# rw-directish-mk-1_0.net
KiCad netlist of a schematic drawn in EAGLE
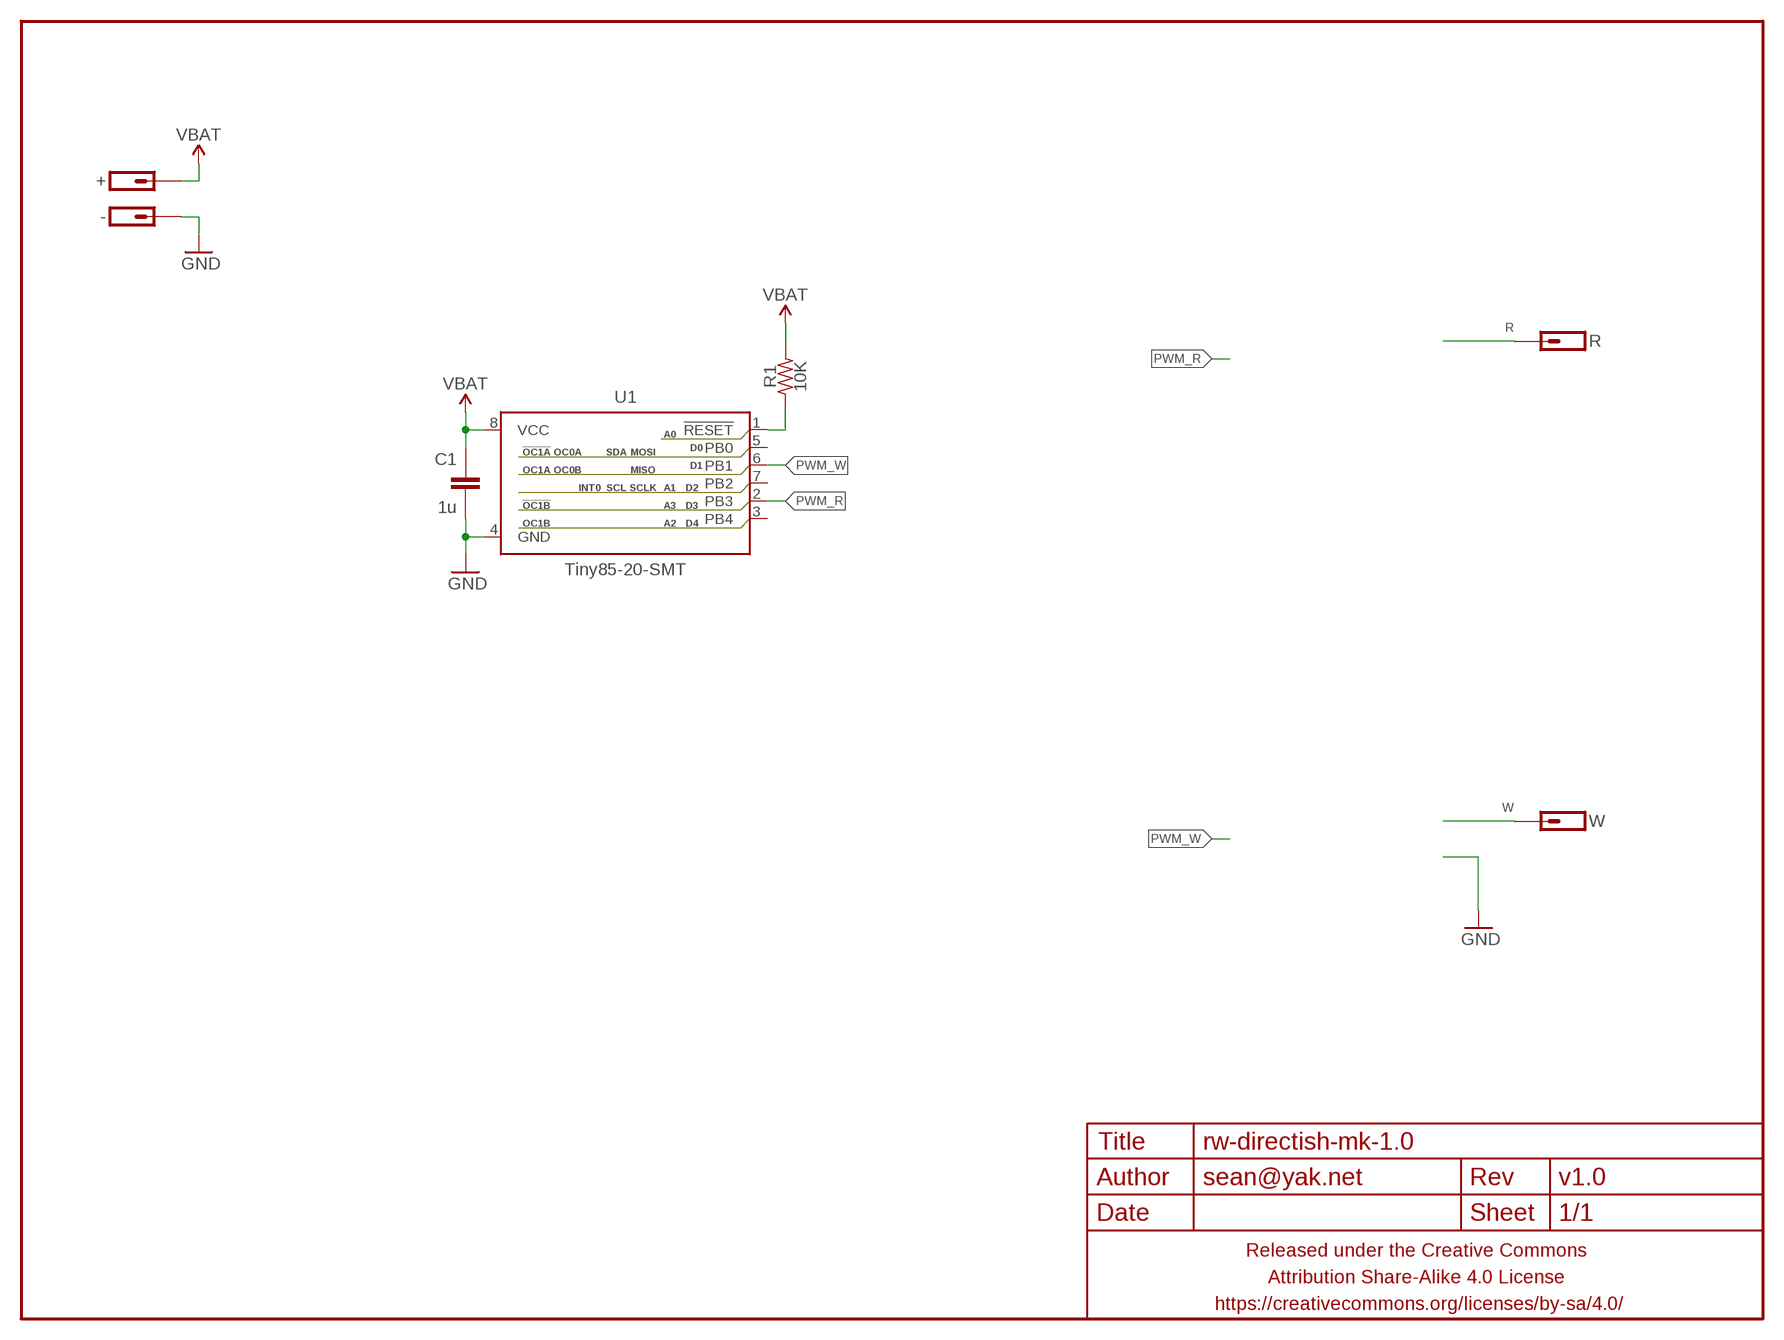
[diagram p0: schematic, sheet 1]

(export (version "E")
  (design (tool "Eeschema 10.0.6"))
  (components
    (comp (ref "+")
      (value "M01PTH-1.2MM-NS")
      (footprint "eagle-import:1X01-1.2MM-NS")
      (libsource (lib "eagle-import") (part "M01PTH-1.2MM-NS"))
    )
    (comp (ref "-")
      (value "M01NOT-A-VIA-NOPE")
      (footprint "eagle-import:1X01_NOSILK_NOSTOP")
      (libsource (lib "eagle-import") (part "M01NOT-A-VIA-NOPE"))
    )
    (comp (ref "C1")
      (value "1u")
      (footprint "eagle-import:C0402")
      (libsource (lib "eagle-import") (part "CAPACITOR-CERAMICC0402"))
    )
    (comp (ref "FRAME1")
      (value "FRAME-LETTERNO_PACKAGE")
      (footprint "eagle-import:DUMMY")
      (fields (field (name "DESIGNER") "sean@yak.net") (field (name "VERSION") "v1.0"))
      (libsource (lib "eagle-import") (part "FRAME-LETTERNO_PACKAGE"))
    )
    (comp (ref "R")
      (value "M01SMD-1.25MM-DIA")
      (footprint "eagle-import:1X01-SMD-1.25MM-DIA-NS")
      (libsource (lib "eagle-import") (part "M01SMD-1.25MM-DIA"))
    )
    (comp (ref "R1")
      (value "10K")
      (footprint "eagle-import:R0402")
      (libsource (lib "eagle-import") (part "RESISTORR0402"))
    )
    (comp (ref "U1")
      (value "Tiny85-20-SMT")
      (footprint "eagle-import:SO08-EIAJ")
      (libsource (lib "eagle-import") (part "ATTINY45TINY85-20-SOICW"))
    )
    (comp (ref "W")
      (value "M01SMD-1.25MM-DIA")
      (footprint "eagle-import:1X01-SMD-1.25MM-DIA-NS")
      (libsource (lib "eagle-import") (part "M01SMD-1.25MM-DIA"))
    )
  )
  (nets
    (net (code "1") (name "/R") (class "Default")
      (node (ref "R") (pin "P$1") (pinfunction "1_P$1") (pintype "passive"))
    )
    (net (code "2") (name "/W") (class "Default")
      (node (ref "W") (pin "P$1") (pinfunction "1_P$1") (pintype "passive"))
    )
    (net (code "3") (name "GND") (class "Default")
      (node (ref "-") (pin "P$1") (pinfunction "1_P$1") (pintype "passive"))
      (node (ref "C1") (pin "2") (pinfunction "2_2") (pintype "passive"))
      (node (ref "U1") (pin "4") (pinfunction "GND_4") (pintype "bidirectional"))
    )
    (net (code "4") (name "Net-(U1-~{RESET})") (class "Default")
      (node (ref "R1") (pin "1") (pinfunction "1_1") (pintype "passive"))
      (node (ref "U1") (pin "1") (pinfunction "~{RESET}_1") (pintype "bidirectional"))
    )
    (net (code "5") (name "PWM_R") (class "Default")
      (node (ref "U1") (pin "2") (pinfunction "PB3_2") (pintype "bidirectional"))
    )
    (net (code "6") (name "PWM_W") (class "Default")
      (node (ref "U1") (pin "6") (pinfunction "PB1_6") (pintype "bidirectional"))
    )
    (net (code "7") (name "VBAT") (class "Default")
      (node (ref "+") (pin "P$1") (pinfunction "1_P$1") (pintype "passive"))
      (node (ref "C1") (pin "1") (pinfunction "1_1") (pintype "passive"))
      (node (ref "R1") (pin "2") (pinfunction "2_2") (pintype "passive"))
      (node (ref "U1") (pin "8") (pinfunction "VCC_8") (pintype "bidirectional"))
    )
    (net (code "8") (name "unconnected-(U1-PB0-Pad5)") (class "Default")
      (node (ref "U1") (pin "5") (pinfunction "PB0_5") (pintype "bidirectional"))
    )
    (net (code "9") (name "unconnected-(U1-PB2-Pad7)") (class "Default")
      (node (ref "U1") (pin "7") (pinfunction "PB2_7") (pintype "bidirectional"))
    )
    (net (code "10") (name "unconnected-(U1-PB4-Pad3)") (class "Default")
      (node (ref "U1") (pin "3") (pinfunction "PB4_3") (pintype "bidirectional"))
    )
  )
)
